# teensy-jst_01_4_v5.net
KiCad netlist of a schematic drawn in EAGLE
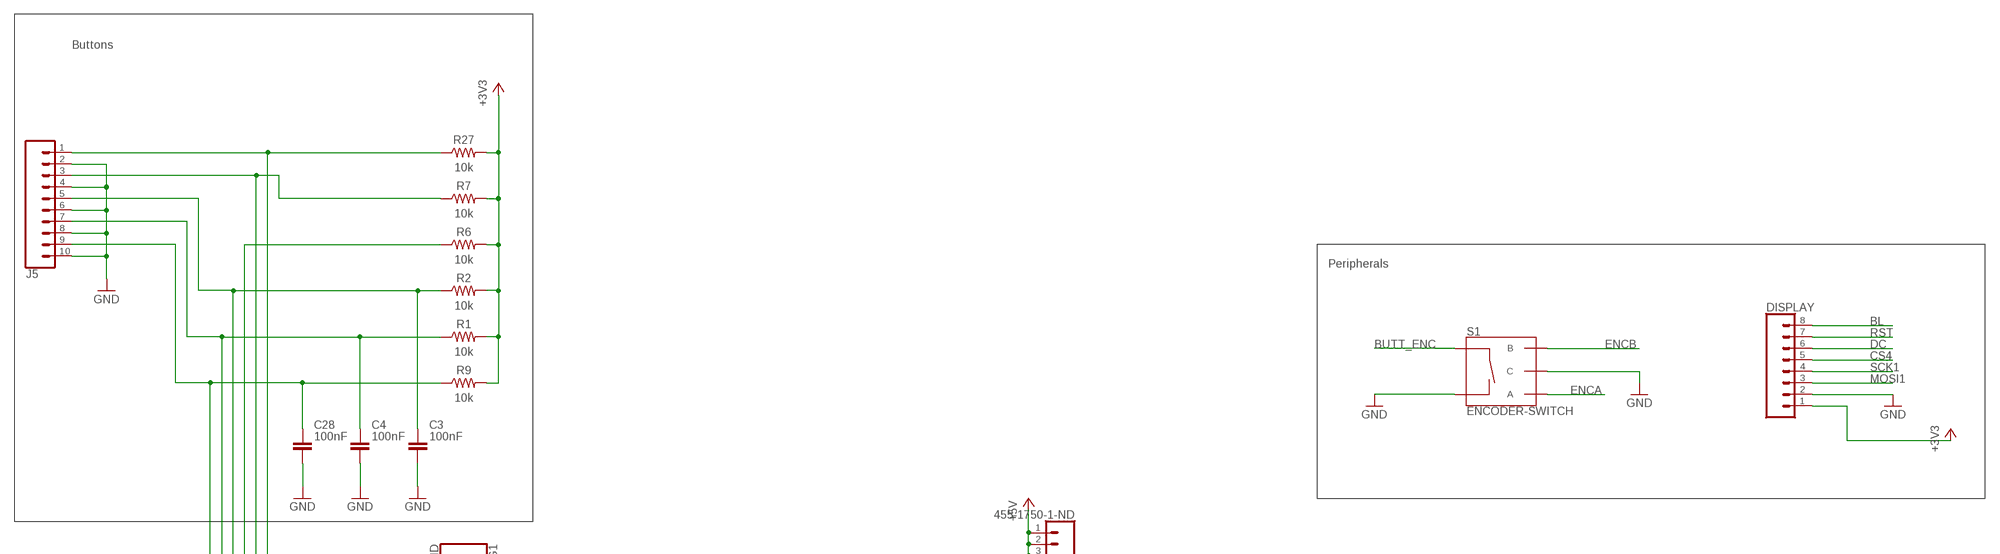
[diagram p0: schematic, sheet 1, part 1 of 3]
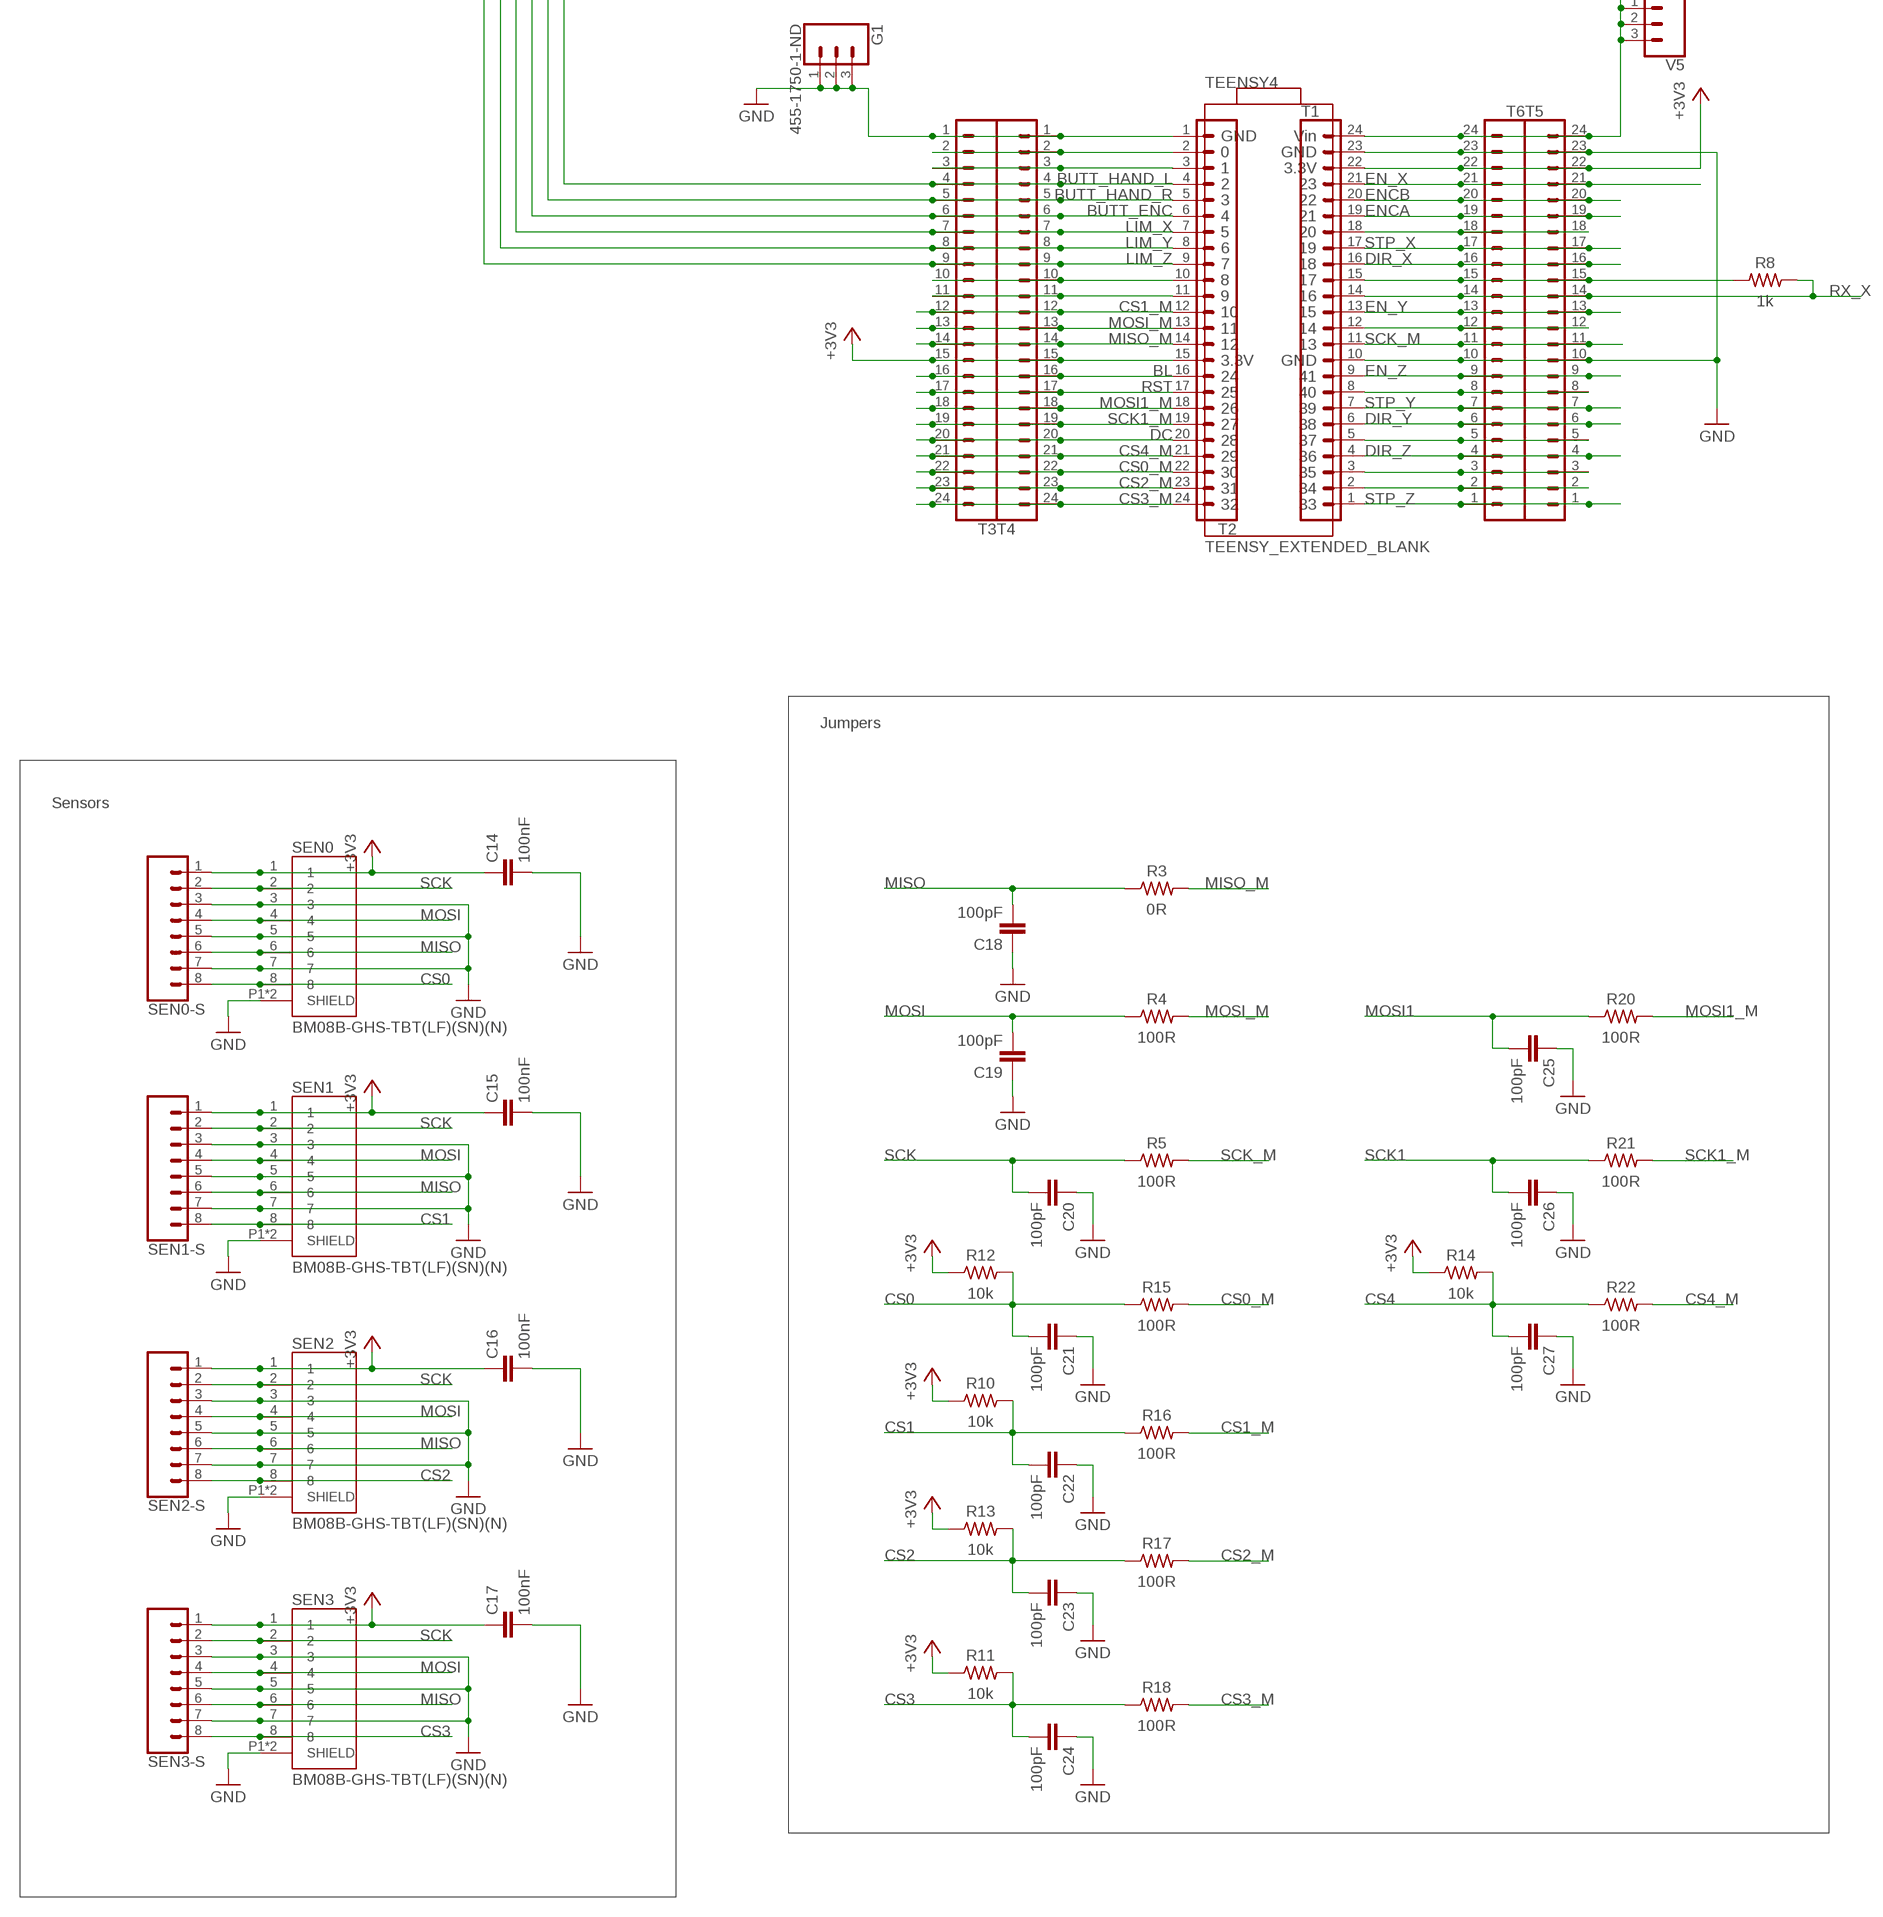
[diagram p1: schematic, sheet 1, part 2 of 3]
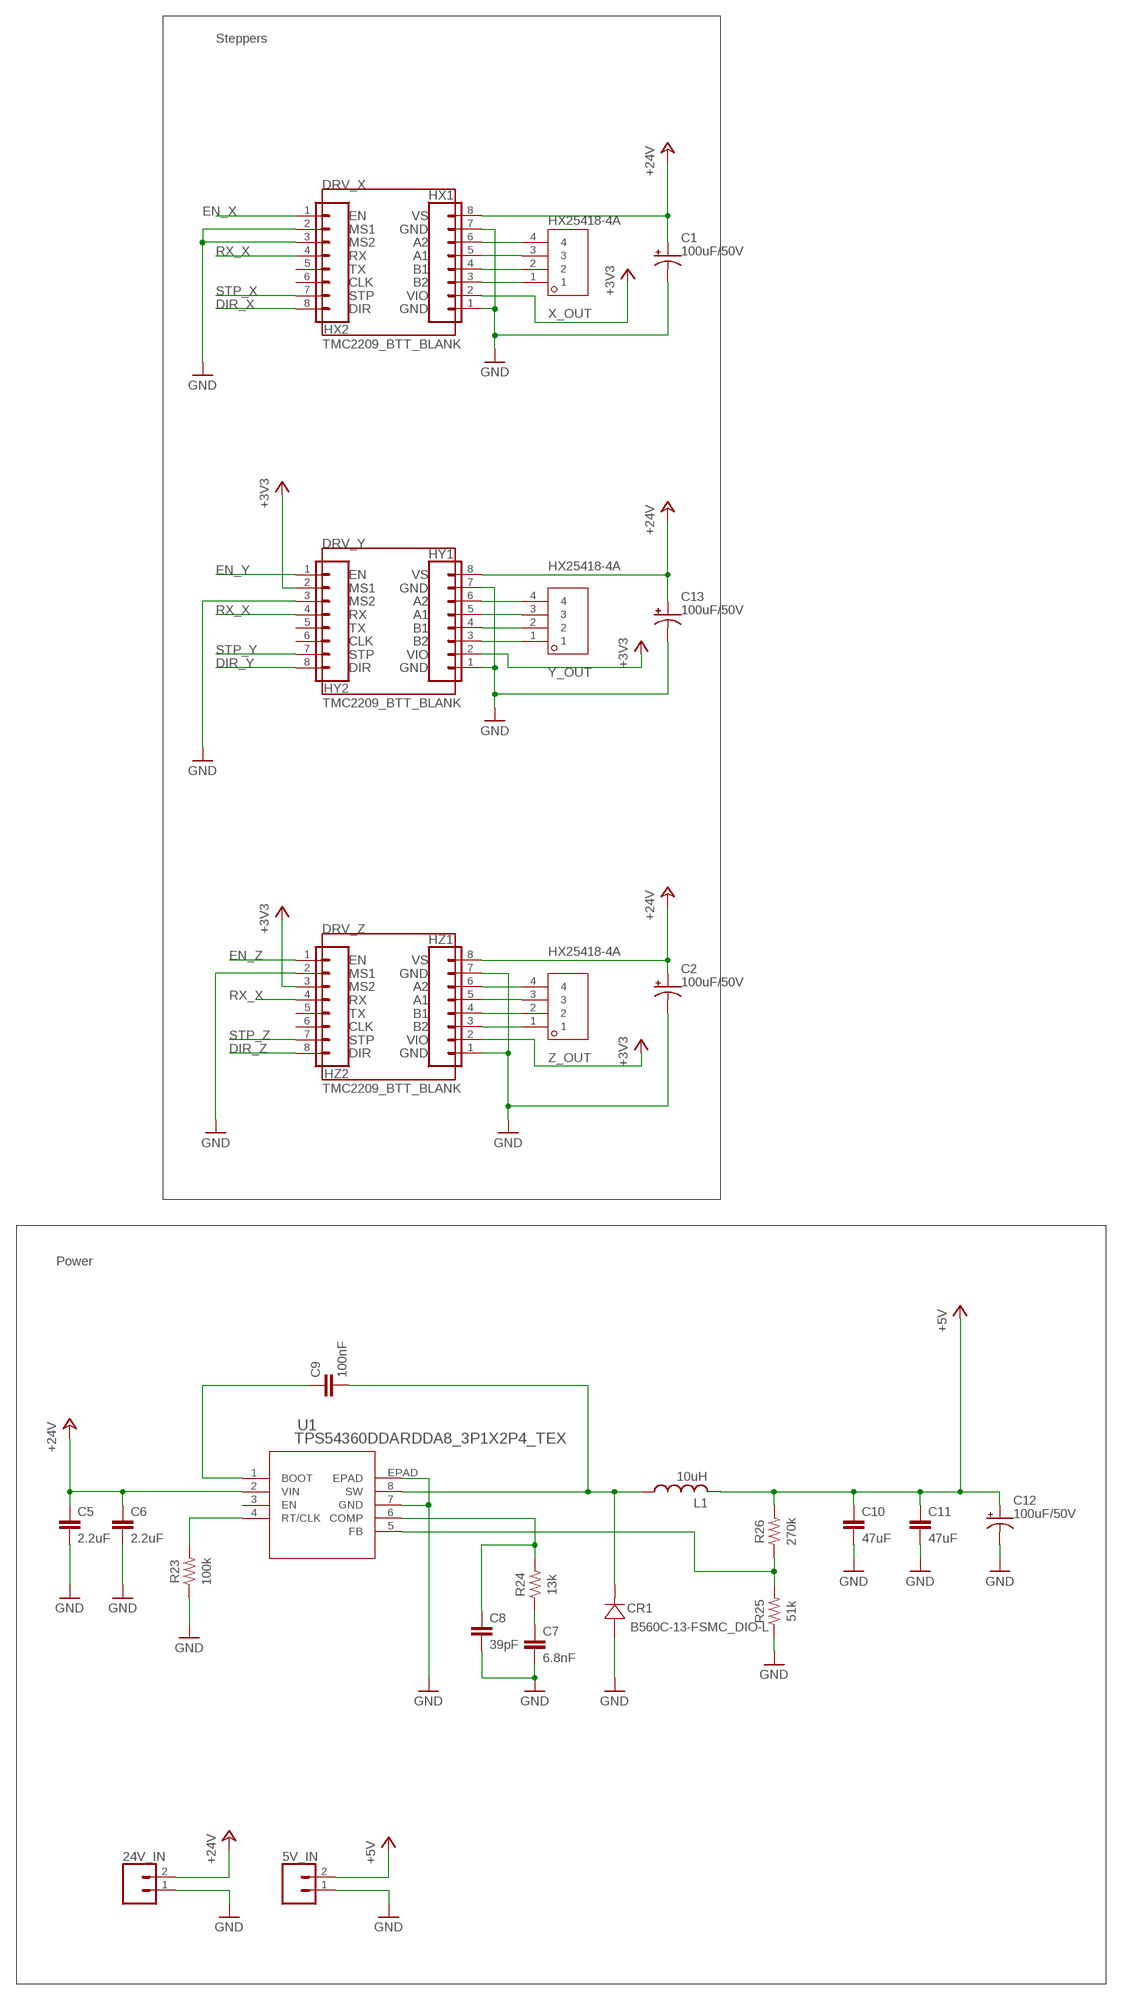
[diagram p2: schematic, sheet 1, part 3 of 3]

(export (version "E")
  (design (tool "Eeschema 10.0.6"))
  (components
    (comp (ref "5V_IN")
      (value "CONN_025MM")
      (footprint "eagle-import:SCREWTERMINAL-5MM-2")
      (libsource (lib "eagle-import") (part "CONN_025MM"))
    )
    (comp (ref "24V_IN")
      (value "CONN_025MM")
      (footprint "eagle-import:SCREWTERMINAL-5MM-2")
      (libsource (lib "eagle-import") (part "CONN_025MM"))
    )
    (comp (ref "C1")
      (value "100uF/50V")
      (footprint "eagle-import:PANASONIC_D")
      (libsource (lib "eagle-import") (part "CPOL-USD"))
    )
    (comp (ref "C2")
      (value "100uF/50V")
      (footprint "eagle-import:PANASONIC_D")
      (libsource (lib "eagle-import") (part "CPOL-USD"))
    )
    (comp (ref "C3")
      (value "100nF")
      (footprint "eagle-import:C0603")
      (libsource (lib "eagle-import") (part "C-EUC0603"))
    )
    (comp (ref "C4")
      (value "100nF")
      (footprint "eagle-import:C0603")
      (libsource (lib "eagle-import") (part "C-EUC0603"))
    )
    (comp (ref "C5")
      (value "2.2uF")
      (footprint "eagle-import:C0603")
      (libsource (lib "eagle-import") (part "C-EUC0603"))
    )
    (comp (ref "C6")
      (value "2.2uF")
      (footprint "eagle-import:C0603")
      (libsource (lib "eagle-import") (part "C-EUC0603"))
    )
    (comp (ref "C7")
      (value "6.8nF")
      (footprint "eagle-import:C0603")
      (libsource (lib "eagle-import") (part "C-EUC0603"))
    )
    (comp (ref "C8")
      (value "39pF")
      (footprint "eagle-import:C0402")
      (libsource (lib "eagle-import") (part "C-EUC0402"))
    )
    (comp (ref "C9")
      (value "100nF")
      (footprint "eagle-import:C0402")
      (libsource (lib "eagle-import") (part "C-EUC0402"))
    )
    (comp (ref "C10")
      (value "47uF")
      (footprint "eagle-import:C0805")
      (libsource (lib "eagle-import") (part "C-EUC0805"))
    )
    (comp (ref "C11")
      (value "47uF")
      (footprint "eagle-import:C0805")
      (libsource (lib "eagle-import") (part "C-EUC0805"))
    )
    (comp (ref "C12")
      (value "100uF/50V")
      (footprint "eagle-import:PANASONIC_D")
      (libsource (lib "eagle-import") (part "CPOL-USD"))
    )
    (comp (ref "C13")
      (value "100uF/50V")
      (footprint "eagle-import:PANASONIC_D")
      (libsource (lib "eagle-import") (part "CPOL-USD"))
    )
    (comp (ref "C14")
      (value "100nF")
      (footprint "eagle-import:C0402")
      (libsource (lib "eagle-import") (part "C-EUC0402"))
    )
    (comp (ref "C15")
      (value "100nF")
      (footprint "eagle-import:C0402")
      (libsource (lib "eagle-import") (part "C-EUC0402"))
    )
    (comp (ref "C16")
      (value "100nF")
      (footprint "eagle-import:C0402")
      (libsource (lib "eagle-import") (part "C-EUC0402"))
    )
    (comp (ref "C17")
      (value "100nF")
      (footprint "eagle-import:C0402")
      (libsource (lib "eagle-import") (part "C-EUC0402"))
    )
    (comp (ref "C18")
      (value "100pF")
      (footprint "eagle-import:C0402K")
      (libsource (lib "eagle-import") (part "C-EUC0402K"))
    )
    (comp (ref "C19")
      (value "100pF")
      (footprint "eagle-import:C0402K")
      (libsource (lib "eagle-import") (part "C-EUC0402K"))
    )
    (comp (ref "C20")
      (value "100pF")
      (footprint "eagle-import:C0402K")
      (libsource (lib "eagle-import") (part "C-EUC0402K"))
    )
    (comp (ref "C21")
      (value "100pF")
      (footprint "eagle-import:C0402K")
      (libsource (lib "eagle-import") (part "C-EUC0402K"))
    )
    (comp (ref "C22")
      (value "100pF")
      (footprint "eagle-import:C0402")
      (libsource (lib "eagle-import") (part "C-EUC0402"))
    )
    (comp (ref "C23")
      (value "100pF")
      (footprint "eagle-import:C0402K")
      (libsource (lib "eagle-import") (part "C-EUC0402K"))
    )
    (comp (ref "C24")
      (value "100pF")
      (footprint "eagle-import:C0402K")
      (libsource (lib "eagle-import") (part "C-EUC0402K"))
    )
    (comp (ref "C25")
      (value "100pF")
      (footprint "eagle-import:C0402K")
      (libsource (lib "eagle-import") (part "C-EUC0402K"))
    )
    (comp (ref "C26")
      (value "100pF")
      (footprint "eagle-import:C0402K")
      (libsource (lib "eagle-import") (part "C-EUC0402K"))
    )
    (comp (ref "C27")
      (value "100pF")
      (footprint "eagle-import:C0402K")
      (libsource (lib "eagle-import") (part "C-EUC0402K"))
    )
    (comp (ref "C28")
      (value "100nF")
      (footprint "eagle-import:C0603")
      (libsource (lib "eagle-import") (part "C-EUC0603"))
    )
    (comp (ref "CR1")
      (value "B560C-13-FSMC_DIO-L")
      (footprint "eagle-import:SMC_DIO-L")
      (fields
        (field (name "MANUFACTURER_PART_NUMBER") "B560C-13-F")
        (field (name "COPYRIGHT") "Copyright (C) 2024 Ultra Librarian. All rights reserved.")
      )
      (libsource (lib "eagle-import") (part "B560C-13-FSMC_DIO-L"))
    )
    (comp (ref "DISPLAY")
      (value "CONN_08\"")
      (footprint "eagle-import:1X08")
      (libsource (lib "eagle-import") (part "CONN_08{dblquote}"))
    )
    (comp (ref "DRV_X")
      (value "TMC2209_BTT_BLANK")
      (footprint "eagle-import:MODULE_TMC2209_BTT_BLANK")
      (libsource (lib "eagle-import") (part "TMC2209_BTT_BLANK"))
    )
    (comp (ref "DRV_Y")
      (value "TMC2209_BTT_BLANK")
      (footprint "eagle-import:MODULE_TMC2209_BTT_BLANK")
      (libsource (lib "eagle-import") (part "TMC2209_BTT_BLANK"))
    )
    (comp (ref "DRV_Z")
      (value "TMC2209_BTT_BLANK")
      (footprint "eagle-import:MODULE_TMC2209_BTT_BLANK")
      (libsource (lib "eagle-import") (part "TMC2209_BTT_BLANK"))
    )
    (comp (ref "G1")
      (value "455-1750-1-ND")
      (footprint "eagle-import:1X03")
      (libsource (lib "eagle-import") (part "CONN_03"))
    )
    (comp (ref "HX1")
      (value "CONN_08\"")
      (footprint "eagle-import:1X08")
      (libsource (lib "eagle-import") (part "CONN_08{dblquote}"))
    )
    (comp (ref "HX2")
      (value "CONN_08\"")
      (footprint "eagle-import:1X08")
      (libsource (lib "eagle-import") (part "CONN_08{dblquote}"))
    )
    (comp (ref "HY1")
      (value "CONN_08\"")
      (footprint "eagle-import:1X08")
      (libsource (lib "eagle-import") (part "CONN_08{dblquote}"))
    )
    (comp (ref "HY2")
      (value "CONN_08\"")
      (footprint "eagle-import:1X08")
      (libsource (lib "eagle-import") (part "CONN_08{dblquote}"))
    )
    (comp (ref "HZ1")
      (value "CONN_08\"")
      (footprint "eagle-import:1X08")
      (libsource (lib "eagle-import") (part "CONN_08{dblquote}"))
    )
    (comp (ref "HZ2")
      (value "CONN_08\"")
      (footprint "eagle-import:1X08")
      (libsource (lib "eagle-import") (part "CONN_08{dblquote}"))
    )
    (comp (ref "J5")
      (value "CONN_10\"")
      (footprint "eagle-import:1X10")
      (libsource (lib "eagle-import") (part "CONN_10{dblquote}"))
    )
    (comp (ref "L1")
      (value "10uH")
      (footprint "eagle-import:MWSA0503S-100MT")
      (libsource (lib "eagle-import") (part "L-USMWSA0503S-100MT"))
    )
    (comp (ref "R1")
      (value "10k")
      (footprint "eagle-import:RESC1608X60")
      (libsource (lib "eagle-import") (part "R-USCHIP-0603(1608-METRIC)_"))
    )
    (comp (ref "R2")
      (value "10k")
      (footprint "eagle-import:RESC1608X60")
      (libsource (lib "eagle-import") (part "R-USCHIP-0603(1608-METRIC)_"))
    )
    (comp (ref "R3")
      (value "0R")
      (footprint "eagle-import:RESC1608X60")
      (libsource (lib "eagle-import") (part "R-USCHIP-0603(1608-METRIC)_"))
    )
    (comp (ref "R4")
      (value "100R")
      (footprint "eagle-import:RESC1608X60")
      (libsource (lib "eagle-import") (part "R-USCHIP-0603(1608-METRIC)_"))
    )
    (comp (ref "R5")
      (value "100R")
      (footprint "eagle-import:RESC1608X60")
      (libsource (lib "eagle-import") (part "R-USCHIP-0603(1608-METRIC)_"))
    )
    (comp (ref "R6")
      (value "10k")
      (footprint "eagle-import:RESC1608X60")
      (libsource (lib "eagle-import") (part "R-USCHIP-0603(1608-METRIC)_"))
    )
    (comp (ref "R7")
      (value "10k")
      (footprint "eagle-import:RESC1608X60")
      (libsource (lib "eagle-import") (part "R-USCHIP-0603(1608-METRIC)_"))
    )
    (comp (ref "R8")
      (value "1k")
      (footprint "eagle-import:RESC1608X60")
      (libsource (lib "eagle-import") (part "R-USCHIP-0603(1608-METRIC)_"))
    )
    (comp (ref "R9")
      (value "10k")
      (footprint "eagle-import:RESC1608X60")
      (libsource (lib "eagle-import") (part "R-USCHIP-0603(1608-METRIC)_"))
    )
    (comp (ref "R10")
      (value "10k")
      (footprint "eagle-import:RESC1608X60")
      (libsource (lib "eagle-import") (part "R-USCHIP-0603(1608-METRIC)_"))
    )
    (comp (ref "R11")
      (value "10k")
      (footprint "eagle-import:RESC1608X60")
      (libsource (lib "eagle-import") (part "R-USCHIP-0603(1608-METRIC)_"))
    )
    (comp (ref "R12")
      (value "10k")
      (footprint "eagle-import:RESC1608X60")
      (libsource (lib "eagle-import") (part "R-USCHIP-0603(1608-METRIC)_"))
    )
    (comp (ref "R13")
      (value "10k")
      (footprint "eagle-import:RESC1608X60")
      (libsource (lib "eagle-import") (part "R-USCHIP-0603(1608-METRIC)_"))
    )
    (comp (ref "R14")
      (value "10k")
      (footprint "eagle-import:RESC1608X60")
      (libsource (lib "eagle-import") (part "R-USCHIP-0603(1608-METRIC)_"))
    )
    (comp (ref "R15")
      (value "100R")
      (footprint "eagle-import:RESC1608X60")
      (libsource (lib "eagle-import") (part "R-USCHIP-0603(1608-METRIC)_"))
    )
    (comp (ref "R16")
      (value "100R")
      (footprint "eagle-import:RESC1608X60")
      (libsource (lib "eagle-import") (part "R-USCHIP-0603(1608-METRIC)_"))
    )
    (comp (ref "R17")
      (value "100R")
      (footprint "eagle-import:RESC1608X60")
      (libsource (lib "eagle-import") (part "R-USCHIP-0603(1608-METRIC)_"))
    )
    (comp (ref "R18")
      (value "100R")
      (footprint "eagle-import:RESC1608X60")
      (libsource (lib "eagle-import") (part "R-USCHIP-0603(1608-METRIC)_"))
    )
    (comp (ref "R20")
      (value "100R")
      (footprint "eagle-import:RESC1608X60")
      (libsource (lib "eagle-import") (part "R-USCHIP-0603(1608-METRIC)_"))
    )
    (comp (ref "R21")
      (value "100R")
      (footprint "eagle-import:RESC1608X60")
      (libsource (lib "eagle-import") (part "R-USCHIP-0603(1608-METRIC)_"))
    )
    (comp (ref "R22")
      (value "100R")
      (footprint "eagle-import:RESC1608X60")
      (libsource (lib "eagle-import") (part "R-USCHIP-0603(1608-METRIC)_"))
    )
    (comp (ref "R23")
      (value "100k")
      (footprint "eagle-import:RESC1005X40")
      (libsource (lib "eagle-import") (part "R-USCHIP-0402(1005-METRIC)_"))
    )
    (comp (ref "R24")
      (value "13k")
      (footprint "eagle-import:RESC1608X60")
      (libsource (lib "eagle-import") (part "R-USCHIP-0603(1608-METRIC)_"))
    )
    (comp (ref "R25")
      (value "51k")
      (footprint "eagle-import:RESC1608X60")
      (libsource (lib "eagle-import") (part "R-USCHIP-0603(1608-METRIC)_"))
    )
    (comp (ref "R26")
      (value "270k")
      (footprint "eagle-import:RESC1005X40")
      (libsource (lib "eagle-import") (part "R-USCHIP-0402(1005-METRIC)_"))
    )
    (comp (ref "R27")
      (value "10k")
      (footprint "eagle-import:RESC1608X60")
      (libsource (lib "eagle-import") (part "R-USCHIP-0603(1608-METRIC)_"))
    )
    (comp (ref "S1")
      (value "ENCODER-SWITCH")
      (footprint "eagle-import:ROTARY_ENC_PLAIN")
      (libsource (lib "eagle-import") (part "ENCODER-SWITCH"))
    )
    (comp (ref "SEN0")
      (value "BM08B-GHS-TBT(LF)(SN)(N)")
      (footprint "eagle-import:JST_BM08B-GHS-TBT(LF)(SN)(N)")
      (fields (field (name "MF") "JST Sales"))
      (libsource (lib "eagle-import") (part "BM08B-GHS-TBT(LF)(SN)(N)"))
    )
    (comp (ref "SEN0-S")
      (value "CONN_08\"")
      (footprint "eagle-import:1X08")
      (libsource (lib "eagle-import") (part "CONN_08{dblquote}"))
    )
    (comp (ref "SEN1")
      (value "BM08B-GHS-TBT(LF)(SN)(N)")
      (footprint "eagle-import:JST_BM08B-GHS-TBT(LF)(SN)(N)")
      (fields (field (name "MF") "JST Sales"))
      (libsource (lib "eagle-import") (part "BM08B-GHS-TBT(LF)(SN)(N)"))
    )
    (comp (ref "SEN1-S")
      (value "CONN_08\"")
      (footprint "eagle-import:1X08")
      (libsource (lib "eagle-import") (part "CONN_08{dblquote}"))
    )
    (comp (ref "SEN2")
      (value "BM08B-GHS-TBT(LF)(SN)(N)")
      (footprint "eagle-import:JST_BM08B-GHS-TBT(LF)(SN)(N)")
      (fields (field (name "MF") "JST Sales"))
      (libsource (lib "eagle-import") (part "BM08B-GHS-TBT(LF)(SN)(N)"))
    )
    (comp (ref "SEN2-S")
      (value "CONN_08\"")
      (footprint "eagle-import:1X08")
      (libsource (lib "eagle-import") (part "CONN_08{dblquote}"))
    )
    (comp (ref "SEN3")
      (value "BM08B-GHS-TBT(LF)(SN)(N)")
      (footprint "eagle-import:JST_BM08B-GHS-TBT(LF)(SN)(N)")
      (fields (field (name "MF") "JST Sales"))
      (libsource (lib "eagle-import") (part "BM08B-GHS-TBT(LF)(SN)(N)"))
    )
    (comp (ref "SEN3-S")
      (value "CONN_08\"")
      (footprint "eagle-import:1X08")
      (libsource (lib "eagle-import") (part "CONN_08{dblquote}"))
    )
    (comp (ref "T1")
      (value "CONN_24")
      (footprint "eagle-import:1X24")
      (libsource (lib "eagle-import") (part "CONN_24"))
    )
    (comp (ref "T2")
      (value "CONN_24")
      (footprint "eagle-import:1X24")
      (libsource (lib "eagle-import") (part "CONN_24"))
    )
    (comp (ref "T3")
      (value "CONN_24")
      (footprint "eagle-import:1X24")
      (libsource (lib "eagle-import") (part "CONN_24"))
    )
    (comp (ref "T4")
      (value "CONN_24")
      (footprint "eagle-import:1X24")
      (libsource (lib "eagle-import") (part "CONN_24"))
    )
    (comp (ref "T5")
      (value "CONN_24")
      (footprint "eagle-import:1X24")
      (libsource (lib "eagle-import") (part "CONN_24"))
    )
    (comp (ref "T6")
      (value "CONN_24")
      (footprint "eagle-import:1X24")
      (libsource (lib "eagle-import") (part "CONN_24"))
    )
    (comp (ref "TEENSY4")
      (value "TEENSY_EXTENDED_BLANK")
      (footprint "eagle-import:TEENSY_EXTENDED_BLANK")
      (libsource (lib "eagle-import") (part "TEENSY_EXTENDED_BLANK"))
    )
    (comp (ref "U1")
      (value "TPS54360DDARDDA8_3P1X2P4_TEX")
      (footprint "eagle-import:DDA8_3P1X2P4_TEX")
      (fields
        (field (name "MANUFACTURER_PART_NUMBER") "TPS54360DDAR")
        (field (name "COPYRIGHT") "Copyright (C) 2024 Ultra Librarian. All rights reserved.")
      )
      (libsource (lib "eagle-import") (part "TPS54360DDARDDA8_3P1X2P4_TEX"))
    )
    (comp (ref "V5")
      (value "455-1750-1-ND")
      (footprint "eagle-import:1X03")
      (libsource (lib "eagle-import") (part "CONN_03"))
    )
    (comp (ref "X_OUT")
      (value "HX25418-4A")
      (footprint "eagle-import:HX25418-4A")
      (libsource (lib "eagle-import") (part "HX25418-4A"))
    )
    (comp (ref "Y_OUT")
      (value "HX25418-4A")
      (footprint "eagle-import:HX25418-4A")
      (libsource (lib "eagle-import") (part "HX25418-4A"))
    )
    (comp (ref "Z_OUT")
      (value "HX25418-4A")
      (footprint "eagle-import:HX25418-4A")
      (libsource (lib "eagle-import") (part "HX25418-4A"))
    )
  )
  (nets
    (net (code "1") (name "+3V3") (class "Default")
      (node (ref "C14") (pin "1") (pinfunction "1_1") (pintype "passive"))
      (node (ref "C15") (pin "1") (pinfunction "1_1") (pintype "passive"))
      (node (ref "C16") (pin "1") (pinfunction "1_1") (pintype "passive"))
      (node (ref "C17") (pin "1") (pinfunction "1_1") (pintype "passive"))
      (node (ref "DISPLAY") (pin "1") (pinfunction "1_1") (pintype "passive"))
      (node (ref "HX1") (pin "2") (pinfunction "2_2") (pintype "passive"))
      (node (ref "HY1") (pin "2") (pinfunction "2_2") (pintype "passive"))
      (node (ref "HY2") (pin "2") (pinfunction "2_2") (pintype "passive"))
      (node (ref "HZ1") (pin "2") (pinfunction "2_2") (pintype "passive"))
      (node (ref "HZ2") (pin "3") (pinfunction "3_3") (pintype "passive"))
      (node (ref "R1") (pin "2") (pinfunction "2_2") (pintype "passive"))
      (node (ref "R10") (pin "1") (pinfunction "1_1") (pintype "passive"))
      (node (ref "R11") (pin "1") (pinfunction "1_1") (pintype "passive"))
      (node (ref "R12") (pin "1") (pinfunction "1_1") (pintype "passive"))
      (node (ref "R13") (pin "1") (pinfunction "1_1") (pintype "passive"))
      (node (ref "R14") (pin "1") (pinfunction "1_1") (pintype "passive"))
      (node (ref "R2") (pin "2") (pinfunction "2_2") (pintype "passive"))
      (node (ref "R27") (pin "2") (pinfunction "2_2") (pintype "passive"))
      (node (ref "R6") (pin "2") (pinfunction "2_2") (pintype "passive"))
      (node (ref "R7") (pin "2") (pinfunction "2_2") (pintype "passive"))
      (node (ref "R9") (pin "2") (pinfunction "2_2") (pintype "passive"))
      (node (ref "SEN0") (pin "1") (pinfunction "1_1") (pintype "passive"))
      (node (ref "SEN0-S") (pin "1") (pinfunction "1_1") (pintype "passive"))
      (node (ref "SEN1") (pin "1") (pinfunction "1_1") (pintype "passive"))
      (node (ref "SEN1-S") (pin "1") (pinfunction "1_1") (pintype "passive"))
      (node (ref "SEN2") (pin "1") (pinfunction "1_1") (pintype "passive"))
      (node (ref "SEN2-S") (pin "1") (pinfunction "1_1") (pintype "passive"))
      (node (ref "SEN3") (pin "1") (pinfunction "1_1") (pintype "passive"))
      (node (ref "SEN3-S") (pin "1") (pinfunction "1_1") (pintype "passive"))
      (node (ref "T1") (pin "22") (pinfunction "22_22") (pintype "passive"))
      (node (ref "T2") (pin "15") (pinfunction "15_15") (pintype "passive"))
      (node (ref "T3") (pin "15") (pinfunction "15_15") (pintype "passive"))
      (node (ref "T4") (pin "15") (pinfunction "15_15") (pintype "passive"))
      (node (ref "T5") (pin "22") (pinfunction "22_22") (pintype "passive"))
      (node (ref "T6") (pin "22") (pinfunction "22_22") (pintype "passive"))
    )
    (net (code "2") (name "+5V") (class "Default")
      (node (ref "5V_IN") (pin "2") (pinfunction "2_2") (pintype "passive"))
      (node (ref "C10") (pin "1") (pinfunction "1_1") (pintype "passive"))
      (node (ref "C11") (pin "1") (pinfunction "1_1") (pintype "passive"))
      (node (ref "C12") (pin "+") (pinfunction "+_+") (pintype "passive"))
      (node (ref "L1") (pin "2") (pinfunction "2_2") (pintype "passive"))
      (node (ref "R26") (pin "2") (pinfunction "2_2") (pintype "passive"))
      (node (ref "T1") (pin "24") (pinfunction "24_24") (pintype "passive"))
      (node (ref "T5") (pin "24") (pinfunction "24_24") (pintype "passive"))
      (node (ref "T6") (pin "24") (pinfunction "24_24") (pintype "passive"))
      (node (ref "V5") (pin "1") (pinfunction "1_1") (pintype "passive"))
      (node (ref "V5") (pin "2") (pinfunction "2_2") (pintype "passive"))
      (node (ref "V5") (pin "3") (pinfunction "3_3") (pintype "passive"))
    )
    (net (code "3") (name "+24V") (class "Default")
      (node (ref "24V_IN") (pin "2") (pinfunction "2_2") (pintype "passive"))
      (node (ref "C1") (pin "+") (pinfunction "+_+") (pintype "passive"))
      (node (ref "C13") (pin "+") (pinfunction "+_+") (pintype "passive"))
      (node (ref "C2") (pin "+") (pinfunction "+_+") (pintype "passive"))
      (node (ref "C5") (pin "1") (pinfunction "1_1") (pintype "passive"))
      (node (ref "C6") (pin "1") (pinfunction "1_1") (pintype "passive"))
      (node (ref "HX1") (pin "8") (pinfunction "8_8") (pintype "passive"))
      (node (ref "HY1") (pin "8") (pinfunction "8_8") (pintype "passive"))
      (node (ref "HZ1") (pin "8") (pinfunction "8_8") (pintype "passive"))
      (node (ref "U1") (pin "2") (pinfunction "VIN_2") (pintype "input"))
    )
    (net (code "4") (name "/BL") (class "Default")
      (node (ref "DISPLAY") (pin "8") (pinfunction "8_8") (pintype "passive"))
      (node (ref "T2") (pin "16") (pinfunction "16_16") (pintype "passive"))
      (node (ref "T3") (pin "16") (pinfunction "16_16") (pintype "passive"))
      (node (ref "T4") (pin "16") (pinfunction "16_16") (pintype "passive"))
    )
    (net (code "5") (name "/BUTT_ENC") (class "Default")
      (node (ref "R6") (pin "1") (pinfunction "1_1") (pintype "passive"))
      (node (ref "S1") (pin "SW+") (pinfunction "SW+_SW+") (pintype "bidirectional"))
      (node (ref "T2") (pin "6") (pinfunction "6_6") (pintype "passive"))
      (node (ref "T3") (pin "6") (pinfunction "6_6") (pintype "passive"))
      (node (ref "T4") (pin "6") (pinfunction "6_6") (pintype "passive"))
    )
    (net (code "6") (name "/BUTT_HAND_L") (class "Default")
      (node (ref "J5") (pin "1") (pinfunction "1_1") (pintype "passive"))
      (node (ref "R27") (pin "1") (pinfunction "1_1") (pintype "passive"))
      (node (ref "T2") (pin "4") (pinfunction "4_4") (pintype "passive"))
      (node (ref "T3") (pin "4") (pinfunction "4_4") (pintype "passive"))
      (node (ref "T4") (pin "4") (pinfunction "4_4") (pintype "passive"))
    )
    (net (code "7") (name "/BUTT_HAND_R") (class "Default")
      (node (ref "J5") (pin "3") (pinfunction "3_3") (pintype "passive"))
      (node (ref "R7") (pin "1") (pinfunction "1_1") (pintype "passive"))
      (node (ref "T2") (pin "5") (pinfunction "5_5") (pintype "passive"))
      (node (ref "T3") (pin "5") (pinfunction "5_5") (pintype "passive"))
      (node (ref "T4") (pin "5") (pinfunction "5_5") (pintype "passive"))
    )
    (net (code "8") (name "/CS0") (class "Default")
      (node (ref "C21") (pin "2") (pinfunction "2_2") (pintype "passive"))
      (node (ref "R12") (pin "2") (pinfunction "2_2") (pintype "passive"))
      (node (ref "R15") (pin "1") (pinfunction "1_1") (pintype "passive"))
      (node (ref "SEN0") (pin "8") (pinfunction "8_8") (pintype "passive"))
      (node (ref "SEN0-S") (pin "8") (pinfunction "8_8") (pintype "passive"))
    )
    (net (code "9") (name "/CS0_M") (class "Default")
      (node (ref "R15") (pin "2") (pinfunction "2_2") (pintype "passive"))
      (node (ref "T2") (pin "22") (pinfunction "22_22") (pintype "passive"))
      (node (ref "T3") (pin "22") (pinfunction "22_22") (pintype "passive"))
      (node (ref "T4") (pin "22") (pinfunction "22_22") (pintype "passive"))
    )
    (net (code "10") (name "/CS1") (class "Default")
      (node (ref "C22") (pin "2") (pinfunction "2_2") (pintype "passive"))
      (node (ref "R10") (pin "2") (pinfunction "2_2") (pintype "passive"))
      (node (ref "R16") (pin "1") (pinfunction "1_1") (pintype "passive"))
      (node (ref "SEN1") (pin "8") (pinfunction "8_8") (pintype "passive"))
      (node (ref "SEN1-S") (pin "8") (pinfunction "8_8") (pintype "passive"))
    )
    (net (code "11") (name "/CS1_M") (class "Default")
      (node (ref "R16") (pin "2") (pinfunction "2_2") (pintype "passive"))
      (node (ref "T2") (pin "12") (pinfunction "12_12") (pintype "passive"))
      (node (ref "T3") (pin "12") (pinfunction "12_12") (pintype "passive"))
      (node (ref "T4") (pin "12") (pinfunction "12_12") (pintype "passive"))
    )
    (net (code "12") (name "/CS2") (class "Default")
      (node (ref "C23") (pin "2") (pinfunction "2_2") (pintype "passive"))
      (node (ref "R13") (pin "2") (pinfunction "2_2") (pintype "passive"))
      (node (ref "R17") (pin "1") (pinfunction "1_1") (pintype "passive"))
      (node (ref "SEN2") (pin "8") (pinfunction "8_8") (pintype "passive"))
      (node (ref "SEN2-S") (pin "8") (pinfunction "8_8") (pintype "passive"))
    )
    (net (code "13") (name "/CS2_M") (class "Default")
      (node (ref "R17") (pin "2") (pinfunction "2_2") (pintype "passive"))
      (node (ref "T2") (pin "23") (pinfunction "23_23") (pintype "passive"))
      (node (ref "T3") (pin "23") (pinfunction "23_23") (pintype "passive"))
      (node (ref "T4") (pin "23") (pinfunction "23_23") (pintype "passive"))
    )
    (net (code "14") (name "/CS3") (class "Default")
      (node (ref "C24") (pin "2") (pinfunction "2_2") (pintype "passive"))
      (node (ref "R11") (pin "2") (pinfunction "2_2") (pintype "passive"))
      (node (ref "R18") (pin "1") (pinfunction "1_1") (pintype "passive"))
      (node (ref "SEN3") (pin "8") (pinfunction "8_8") (pintype "passive"))
      (node (ref "SEN3-S") (pin "8") (pinfunction "8_8") (pintype "passive"))
    )
    (net (code "15") (name "/CS3_M") (class "Default")
      (node (ref "R18") (pin "2") (pinfunction "2_2") (pintype "passive"))
      (node (ref "T2") (pin "24") (pinfunction "24_24") (pintype "passive"))
      (node (ref "T3") (pin "24") (pinfunction "24_24") (pintype "passive"))
      (node (ref "T4") (pin "24") (pinfunction "24_24") (pintype "passive"))
    )
    (net (code "16") (name "/CS4") (class "Default")
      (node (ref "C27") (pin "2") (pinfunction "2_2") (pintype "passive"))
      (node (ref "DISPLAY") (pin "5") (pinfunction "5_5") (pintype "passive"))
      (node (ref "R14") (pin "2") (pinfunction "2_2") (pintype "passive"))
      (node (ref "R22") (pin "1") (pinfunction "1_1") (pintype "passive"))
    )
    (net (code "17") (name "/CS4_M") (class "Default")
      (node (ref "R22") (pin "2") (pinfunction "2_2") (pintype "passive"))
      (node (ref "T2") (pin "21") (pinfunction "21_21") (pintype "passive"))
      (node (ref "T3") (pin "21") (pinfunction "21_21") (pintype "passive"))
      (node (ref "T4") (pin "21") (pinfunction "21_21") (pintype "passive"))
    )
    (net (code "18") (name "/DC") (class "Default")
      (node (ref "DISPLAY") (pin "6") (pinfunction "6_6") (pintype "passive"))
      (node (ref "T2") (pin "20") (pinfunction "20_20") (pintype "passive"))
      (node (ref "T3") (pin "20") (pinfunction "20_20") (pintype "passive"))
      (node (ref "T4") (pin "20") (pinfunction "20_20") (pintype "passive"))
    )
    (net (code "19") (name "/DIR_X") (class "Default")
      (node (ref "HX2") (pin "8") (pinfunction "8_8") (pintype "passive"))
      (node (ref "T1") (pin "16") (pinfunction "16_16") (pintype "passive"))
      (node (ref "T5") (pin "16") (pinfunction "16_16") (pintype "passive"))
      (node (ref "T6") (pin "16") (pinfunction "16_16") (pintype "passive"))
    )
    (net (code "20") (name "/DIR_Y") (class "Default")
      (node (ref "HY2") (pin "8") (pinfunction "8_8") (pintype "passive"))
      (node (ref "T1") (pin "6") (pinfunction "6_6") (pintype "passive"))
      (node (ref "T5") (pin "6") (pinfunction "6_6") (pintype "passive"))
      (node (ref "T6") (pin "6") (pinfunction "6_6") (pintype "passive"))
    )
    (net (code "21") (name "/DIR_Z") (class "Default")
      (node (ref "HZ2") (pin "8") (pinfunction "8_8") (pintype "passive"))
      (node (ref "T1") (pin "4") (pinfunction "4_4") (pintype "passive"))
      (node (ref "T5") (pin "4") (pinfunction "4_4") (pintype "passive"))
      (node (ref "T6") (pin "4") (pinfunction "4_4") (pintype "passive"))
    )
    (net (code "22") (name "/ENCA") (class "Default")
      (node (ref "S1") (pin "A") (pinfunction "A_A") (pintype "bidirectional"))
      (node (ref "T1") (pin "19") (pinfunction "19_19") (pintype "passive"))
      (node (ref "T5") (pin "19") (pinfunction "19_19") (pintype "passive"))
      (node (ref "T6") (pin "19") (pinfunction "19_19") (pintype "passive"))
    )
    (net (code "23") (name "/ENCB") (class "Default")
      (node (ref "S1") (pin "B") (pinfunction "B_B") (pintype "bidirectional"))
      (node (ref "T1") (pin "20") (pinfunction "20_20") (pintype "passive"))
      (node (ref "T5") (pin "20") (pinfunction "20_20") (pintype "passive"))
      (node (ref "T6") (pin "20") (pinfunction "20_20") (pintype "passive"))
    )
    (net (code "24") (name "/EN_X") (class "Default")
      (node (ref "HX2") (pin "1") (pinfunction "1_1") (pintype "passive"))
      (node (ref "T1") (pin "21") (pinfunction "21_21") (pintype "passive"))
      (node (ref "T5") (pin "21") (pinfunction "21_21") (pintype "passive"))
      (node (ref "T6") (pin "21") (pinfunction "21_21") (pintype "passive"))
    )
    (net (code "25") (name "/EN_Y") (class "Default")
      (node (ref "HY2") (pin "1") (pinfunction "1_1") (pintype "passive"))
      (node (ref "T1") (pin "13") (pinfunction "13_13") (pintype "passive"))
      (node (ref "T5") (pin "13") (pinfunction "13_13") (pintype "passive"))
      (node (ref "T6") (pin "13") (pinfunction "13_13") (pintype "passive"))
    )
    (net (code "26") (name "/EN_Z") (class "Default")
      (node (ref "HZ2") (pin "1") (pinfunction "1_1") (pintype "passive"))
      (node (ref "T1") (pin "9") (pinfunction "9_9") (pintype "passive"))
      (node (ref "T5") (pin "9") (pinfunction "9_9") (pintype "passive"))
      (node (ref "T6") (pin "9") (pinfunction "9_9") (pintype "passive"))
    )
    (net (code "27") (name "/LIM_X") (class "Default")
      (node (ref "C3") (pin "1") (pinfunction "1_1") (pintype "passive"))
      (node (ref "J5") (pin "5") (pinfunction "5_5") (pintype "passive"))
      (node (ref "R2") (pin "1") (pinfunction "1_1") (pintype "passive"))
      (node (ref "T2") (pin "7") (pinfunction "7_7") (pintype "passive"))
      (node (ref "T3") (pin "7") (pinfunction "7_7") (pintype "passive"))
      (node (ref "T4") (pin "7") (pinfunction "7_7") (pintype "passive"))
    )
    (net (code "28") (name "/LIM_Y") (class "Default")
      (node (ref "C4") (pin "1") (pinfunction "1_1") (pintype "passive"))
      (node (ref "J5") (pin "7") (pinfunction "7_7") (pintype "passive"))
      (node (ref "R1") (pin "1") (pinfunction "1_1") (pintype "passive"))
      (node (ref "T2") (pin "8") (pinfunction "8_8") (pintype "passive"))
      (node (ref "T3") (pin "8") (pinfunction "8_8") (pintype "passive"))
      (node (ref "T4") (pin "8") (pinfunction "8_8") (pintype "passive"))
    )
    (net (code "29") (name "/LIM_Z") (class "Default")
      (node (ref "C28") (pin "1") (pinfunction "1_1") (pintype "passive"))
      (node (ref "J5") (pin "9") (pinfunction "9_9") (pintype "passive"))
      (node (ref "R9") (pin "1") (pinfunction "1_1") (pintype "passive"))
      (node (ref "T2") (pin "9") (pinfunction "9_9") (pintype "passive"))
      (node (ref "T3") (pin "9") (pinfunction "9_9") (pintype "passive"))
      (node (ref "T4") (pin "9") (pinfunction "9_9") (pintype "passive"))
    )
    (net (code "30") (name "/MISO") (class "Default")
      (node (ref "C18") (pin "2") (pinfunction "2_2") (pintype "passive"))
      (node (ref "R3") (pin "1") (pinfunction "1_1") (pintype "passive"))
      (node (ref "SEN0") (pin "6") (pinfunction "6_6") (pintype "passive"))
      (node (ref "SEN0-S") (pin "6") (pinfunction "6_6") (pintype "passive"))
      (node (ref "SEN1") (pin "6") (pinfunction "6_6") (pintype "passive"))
      (node (ref "SEN1-S") (pin "6") (pinfunction "6_6") (pintype "passive"))
      (node (ref "SEN2") (pin "6") (pinfunction "6_6") (pintype "passive"))
      (node (ref "SEN2-S") (pin "6") (pinfunction "6_6") (pintype "passive"))
      (node (ref "SEN3") (pin "6") (pinfunction "6_6") (pintype "passive"))
      (node (ref "SEN3-S") (pin "6") (pinfunction "6_6") (pintype "passive"))
    )
    (net (code "31") (name "/MISO_M") (class "Default")
      (node (ref "R3") (pin "2") (pinfunction "2_2") (pintype "passive"))
      (node (ref "T2") (pin "14") (pinfunction "14_14") (pintype "passive"))
      (node (ref "T3") (pin "14") (pinfunction "14_14") (pintype "passive"))
      (node (ref "T4") (pin "14") (pinfunction "14_14") (pintype "passive"))
    )
    (net (code "32") (name "/MOSI") (class "Default")
      (node (ref "C19") (pin "2") (pinfunction "2_2") (pintype "passive"))
      (node (ref "R4") (pin "1") (pinfunction "1_1") (pintype "passive"))
      (node (ref "SEN0") (pin "4") (pinfunction "4_4") (pintype "passive"))
      (node (ref "SEN0-S") (pin "4") (pinfunction "4_4") (pintype "passive"))
      (node (ref "SEN1") (pin "4") (pinfunction "4_4") (pintype "passive"))
      (node (ref "SEN1-S") (pin "4") (pinfunction "4_4") (pintype "passive"))
      (node (ref "SEN2") (pin "4") (pinfunction "4_4") (pintype "passive"))
      (node (ref "SEN2-S") (pin "4") (pinfunction "4_4") (pintype "passive"))
      (node (ref "SEN3") (pin "4") (pinfunction "4_4") (pintype "passive"))
      (node (ref "SEN3-S") (pin "4") (pinfunction "4_4") (pintype "passive"))
    )
    (net (code "33") (name "/MOSI1") (class "Default")
      (node (ref "C25") (pin "2") (pinfunction "2_2") (pintype "passive"))
      (node (ref "DISPLAY") (pin "3") (pinfunction "3_3") (pintype "passive"))
      (node (ref "R20") (pin "1") (pinfunction "1_1") (pintype "passive"))
    )
    (net (code "34") (name "/MOSI1_M") (class "Default")
      (node (ref "R20") (pin "2") (pinfunction "2_2") (pintype "passive"))
      (node (ref "T2") (pin "18") (pinfunction "18_18") (pintype "passive"))
      (node (ref "T3") (pin "18") (pinfunction "18_18") (pintype "passive"))
      (node (ref "T4") (pin "18") (pinfunction "18_18") (pintype "passive"))
    )
    (net (code "35") (name "/MOSI_M") (class "Default")
      (node (ref "R4") (pin "2") (pinfunction "2_2") (pintype "passive"))
      (node (ref "T2") (pin "13") (pinfunction "13_13") (pintype "passive"))
      (node (ref "T3") (pin "13") (pinfunction "13_13") (pintype "passive"))
      (node (ref "T4") (pin "13") (pinfunction "13_13") (pintype "passive"))
    )
    (net (code "36") (name "/RST") (class "Default")
      (node (ref "DISPLAY") (pin "7") (pinfunction "7_7") (pintype "passive"))
      (node (ref "T2") (pin "17") (pinfunction "17_17") (pintype "passive"))
      (node (ref "T3") (pin "17") (pinfunction "17_17") (pintype "passive"))
      (node (ref "T4") (pin "17") (pinfunction "17_17") (pintype "passive"))
    )
    (net (code "37") (name "/RX_X") (class "Default")
      (node (ref "HX2") (pin "4") (pinfunction "4_4") (pintype "passive"))
      (node (ref "HY2") (pin "4") (pinfunction "4_4") (pintype "passive"))
      (node (ref "HZ2") (pin "4") (pinfunction "4_4") (pintype "passive"))
      (node (ref "R8") (pin "2") (pinfunction "2_2") (pintype "passive"))
      (node (ref "T1") (pin "14") (pinfunction "14_14") (pintype "passive"))
      (node (ref "T5") (pin "14") (pinfunction "14_14") (pintype "passive"))
      (node (ref "T6") (pin "14") (pinfunction "14_14") (pintype "passive"))
    )
    (net (code "38") (name "/SCK") (class "Default")
      (node (ref "C20") (pin "2") (pinfunction "2_2") (pintype "passive"))
      (node (ref "R5") (pin "1") (pinfunction "1_1") (pintype "passive"))
      (node (ref "SEN0") (pin "2") (pinfunction "2_2") (pintype "passive"))
      (node (ref "SEN0-S") (pin "2") (pinfunction "2_2") (pintype "passive"))
      (node (ref "SEN1") (pin "2") (pinfunction "2_2") (pintype "passive"))
      (node (ref "SEN1-S") (pin "2") (pinfunction "2_2") (pintype "passive"))
      (node (ref "SEN2") (pin "2") (pinfunction "2_2") (pintype "passive"))
      (node (ref "SEN2-S") (pin "2") (pinfunction "2_2") (pintype "passive"))
      (node (ref "SEN3") (pin "2") (pinfunction "2_2") (pintype "passive"))
      (node (ref "SEN3-S") (pin "2") (pinfunction "2_2") (pintype "passive"))
    )
    (net (code "39") (name "/SCK1") (class "Default")
      (node (ref "C26") (pin "2") (pinfunction "2_2") (pintype "passive"))
      (node (ref "DISPLAY") (pin "4") (pinfunction "4_4") (pintype "passive"))
      (node (ref "R21") (pin "1") (pinfunction "1_1") (pintype "passive"))
    )
    (net (code "40") (name "/SCK1_M") (class "Default")
      (node (ref "R21") (pin "2") (pinfunction "2_2") (pintype "passive"))
      (node (ref "T2") (pin "19") (pinfunction "19_19") (pintype "passive"))
      (node (ref "T3") (pin "19") (pinfunction "19_19") (pintype "passive"))
      (node (ref "T4") (pin "19") (pinfunction "19_19") (pintype "passive"))
    )
    (net (code "41") (name "/SCK_M") (class "Default")
      (node (ref "R5") (pin "2") (pinfunction "2_2") (pintype "passive"))
      (node (ref "T1") (pin "11") (pinfunction "11_11") (pintype "passive"))
      (node (ref "T5") (pin "11") (pinfunction "11_11") (pintype "passive"))
      (node (ref "T6") (pin "11") (pinfunction "11_11") (pintype "passive"))
    )
    (net (code "42") (name "/STP_X") (class "Default")
      (node (ref "HX2") (pin "7") (pinfunction "7_7") (pintype "passive"))
      (node (ref "T1") (pin "17") (pinfunction "17_17") (pintype "passive"))
      (node (ref "T5") (pin "17") (pinfunction "17_17") (pintype "passive"))
      (node (ref "T6") (pin "17") (pinfunction "17_17") (pintype "passive"))
    )
    (net (code "43") (name "/STP_Y") (class "Default")
      (node (ref "HY2") (pin "7") (pinfunction "7_7") (pintype "passive"))
      (node (ref "T1") (pin "7") (pinfunction "7_7") (pintype "passive"))
      (node (ref "T5") (pin "7") (pinfunction "7_7") (pintype "passive"))
      (node (ref "T6") (pin "7") (pinfunction "7_7") (pintype "passive"))
    )
    (net (code "44") (name "/STP_Z") (class "Default")
      (node (ref "HZ2") (pin "7") (pinfunction "7_7") (pintype "passive"))
      (node (ref "T1") (pin "1") (pinfunction "1_1") (pintype "passive"))
      (node (ref "T5") (pin "1") (pinfunction "1_1") (pintype "passive"))
      (node (ref "T6") (pin "1") (pinfunction "1_1") (pintype "passive"))
    )
    (net (code "45") (name "GND") (class "Default")
      (node (ref "24V_IN") (pin "1") (pinfunction "1_1") (pintype "passive"))
      (node (ref "5V_IN") (pin "1") (pinfunction "1_1") (pintype "passive"))
      (node (ref "C1") (pin "-") (pinfunction "-_-") (pintype "passive"))
      (node (ref "C10") (pin "2") (pinfunction "2_2") (pintype "passive"))
      (node (ref "C11") (pin "2") (pinfunction "2_2") (pintype "passive"))
      (node (ref "C12") (pin "-") (pinfunction "-_-") (pintype "passive"))
      (node (ref "C13") (pin "-") (pinfunction "-_-") (pintype "passive"))
      (node (ref "C14") (pin "2") (pinfunction "2_2") (pintype "passive"))
      (node (ref "C15") (pin "2") (pinfunction "2_2") (pintype "passive"))
      (node (ref "C16") (pin "2") (pinfunction "2_2") (pintype "passive"))
      (node (ref "C17") (pin "2") (pinfunction "2_2") (pintype "passive"))
      (node (ref "C18") (pin "1") (pinfunction "1_1") (pintype "passive"))
      (node (ref "C19") (pin "1") (pinfunction "1_1") (pintype "passive"))
      (node (ref "C2") (pin "-") (pinfunction "-_-") (pintype "passive"))
      (node (ref "C20") (pin "1") (pinfunction "1_1") (pintype "passive"))
      (node (ref "C21") (pin "1") (pinfunction "1_1") (pintype "passive"))
      (node (ref "C22") (pin "1") (pinfunction "1_1") (pintype "passive"))
      (node (ref "C23") (pin "1") (pinfunction "1_1") (pintype "passive"))
      (node (ref "C24") (pin "1") (pinfunction "1_1") (pintype "passive"))
      (node (ref "C25") (pin "1") (pinfunction "1_1") (pintype "passive"))
      (node (ref "C26") (pin "1") (pinfunction "1_1") (pintype "passive"))
      (node (ref "C27") (pin "1") (pinfunction "1_1") (pintype "passive"))
      (node (ref "C28") (pin "2") (pinfunction "2_2") (pintype "passive"))
      (node (ref "C3") (pin "2") (pinfunction "2_2") (pintype "passive"))
      (node (ref "C4") (pin "2") (pinfunction "2_2") (pintype "passive"))
      (node (ref "C5") (pin "2") (pinfunction "2_2") (pintype "passive"))
      (node (ref "C6") (pin "2") (pinfunction "2_2") (pintype "passive"))
      (node (ref "C7") (pin "2") (pinfunction "2_2") (pintype "passive"))
      (node (ref "C8") (pin "2") (pinfunction "2_2") (pintype "passive"))
      (node (ref "CR1") (pin "2") (pinfunction "2_2") (pintype "passive"))
      (node (ref "DISPLAY") (pin "2") (pinfunction "2_2") (pintype "passive"))
      (node (ref "G1") (pin "1") (pinfunction "1_1") (pintype "passive"))
      (node (ref "G1") (pin "2") (pinfunction "2_2") (pintype "passive"))
      (node (ref "G1") (pin "3") (pinfunction "3_3") (pintype "passive"))
      (node (ref "HX1") (pin "1") (pinfunction "1_1") (pintype "passive"))
      (node (ref "HX1") (pin "7") (pinfunction "7_7") (pintype "passive"))
      (node (ref "HX2") (pin "2") (pinfunction "2_2") (pintype "passive"))
      (node (ref "HX2") (pin "3") (pinfunction "3_3") (pintype "passive"))
      (node (ref "HY1") (pin "1") (pinfunction "1_1") (pintype "passive"))
      (node (ref "HY1") (pin "7") (pinfunction "7_7") (pintype "passive"))
      (node (ref "HY2") (pin "3") (pinfunction "3_3") (pintype "passive"))
      (node (ref "HZ1") (pin "1") (pinfunction "1_1") (pintype "passive"))
      (node (ref "HZ1") (pin "7") (pinfunction "7_7") (pintype "passive"))
      (node (ref "HZ2") (pin "2") (pinfunction "2_2") (pintype "passive"))
      (node (ref "J5") (pin "10") (pinfunction "10_10") (pintype "passive"))
      (node (ref "J5") (pin "2") (pinfunction "2_2") (pintype "passive"))
      (node (ref "J5") (pin "4") (pinfunction "4_4") (pintype "passive"))
      (node (ref "J5") (pin "6") (pinfunction "6_6") (pintype "passive"))
      (node (ref "J5") (pin "8") (pinfunction "8_8") (pintype "passive"))
      (node (ref "R23") (pin "1") (pinfunction "1_1") (pintype "passive"))
      (node (ref "R25") (pin "1") (pinfunction "1_1") (pintype "passive"))
      (node (ref "S1") (pin "C") (pinfunction "C_C") (pintype "bidirectional"))
      (node (ref "S1") (pin "SW-") (pinfunction "SW-_SW-") (pintype "bidirectional"))
      (node (ref "SEN0") (pin "3") (pinfunction "3_3") (pintype "passive"))
      (node (ref "SEN0") (pin "5") (pinfunction "5_5") (pintype "passive"))
      (node (ref "SEN0") (pin "7") (pinfunction "7_7") (pintype "passive"))
      (node (ref "SEN0") (pin "P1") (pinfunction "SHIELD_P1") (pintype "passive"))
      (node (ref "SEN0") (pin "P2") (pinfunction "SHIELD_P2") (pintype "passive"))
      (node (ref "SEN0-S") (pin "3") (pinfunction "3_3") (pintype "passive"))
      (node (ref "SEN0-S") (pin "5") (pinfunction "5_5") (pintype "passive"))
      (node (ref "SEN0-S") (pin "7") (pinfunction "7_7") (pintype "passive"))
      (node (ref "SEN1") (pin "3") (pinfunction "3_3") (pintype "passive"))
      (node (ref "SEN1") (pin "5") (pinfunction "5_5") (pintype "passive"))
      (node (ref "SEN1") (pin "7") (pinfunction "7_7") (pintype "passive"))
      (node (ref "SEN1") (pin "P1") (pinfunction "SHIELD_P1") (pintype "passive"))
      (node (ref "SEN1") (pin "P2") (pinfunction "SHIELD_P2") (pintype "passive"))
      (node (ref "SEN1-S") (pin "3") (pinfunction "3_3") (pintype "passive"))
      (node (ref "SEN1-S") (pin "5") (pinfunction "5_5") (pintype "passive"))
      (node (ref "SEN1-S") (pin "7") (pinfunction "7_7") (pintype "passive"))
      (node (ref "SEN2") (pin "3") (pinfunction "3_3") (pintype "passive"))
      (node (ref "SEN2") (pin "5") (pinfunction "5_5") (pintype "passive"))
      (node (ref "SEN2") (pin "7") (pinfunction "7_7") (pintype "passive"))
      (node (ref "SEN2") (pin "P1") (pinfunction "SHIELD_P1") (pintype "passive"))
      (node (ref "SEN2") (pin "P2") (pinfunction "SHIELD_P2") (pintype "passive"))
      (node (ref "SEN2-S") (pin "3") (pinfunction "3_3") (pintype "passive"))
      (node (ref "SEN2-S") (pin "5") (pinfunction "5_5") (pintype "passive"))
      (node (ref "SEN2-S") (pin "7") (pinfunction "7_7") (pintype "passive"))
      (node (ref "SEN3") (pin "3") (pinfunction "3_3") (pintype "passive"))
      (node (ref "SEN3") (pin "5") (pinfunction "5_5") (pintype "passive"))
      (node (ref "SEN3") (pin "7") (pinfunction "7_7") (pintype "passive"))
      (node (ref "SEN3") (pin "P1") (pinfunction "SHIELD_P1") (pintype "passive"))
      (node (ref "SEN3") (pin "P2") (pinfunction "SHIELD_P2") (pintype "passive"))
      (node (ref "SEN3-S") (pin "3") (pinfunction "3_3") (pintype "passive"))
      (node (ref "SEN3-S") (pin "5") (pinfunction "5_5") (pintype "passive"))
      (node (ref "SEN3-S") (pin "7") (pinfunction "7_7") (pintype "passive"))
      (node (ref "T1") (pin "10") (pinfunction "10_10") (pintype "passive"))
      (node (ref "T1") (pin "23") (pinfunction "23_23") (pintype "passive"))
      (node (ref "T2") (pin "1") (pinfunction "1_1") (pintype "passive"))
      (node (ref "T3") (pin "1") (pinfunction "1_1") (pintype "passive"))
      (node (ref "T4") (pin "1") (pinfunction "1_1") (pintype "passive"))
      (node (ref "T5") (pin "10") (pinfunction "10_10") (pintype "passive"))
      (node (ref "T5") (pin "23") (pinfunction "23_23") (pintype "passive"))
      (node (ref "T6") (pin "10") (pinfunction "10_10") (pintype "passive"))
      (node (ref "T6") (pin "23") (pinfunction "23_23") (pintype "passive"))
      (node (ref "U1") (pin "7") (pinfunction "GND_7") (pintype "power_in"))
      (node (ref "U1") (pin "EPAD") (pinfunction "EPAD_EPAD") (pintype "passive"))
    )
    (net (code "46") (name "Net-(C7-Pad1)") (class "Default")
      (node (ref "C7") (pin "1") (pinfunction "1_1") (pintype "passive"))
      (node (ref "R24") (pin "1") (pinfunction "1_1") (pintype "passive"))
    )
    (net (code "47") (name "Net-(HX1-Pad3)") (class "Default")
      (node (ref "HX1") (pin "3") (pinfunction "3_3") (pintype "passive"))
      (node (ref "X_OUT") (pin "1") (pinfunction "1_1") (pintype "bidirectional"))
    )
    (net (code "48") (name "Net-(HX1-Pad4)") (class "Default")
      (node (ref "HX1") (pin "4") (pinfunction "4_4") (pintype "passive"))
      (node (ref "X_OUT") (pin "2") (pinfunction "2_2") (pintype "bidirectional"))
    )
    (net (code "49") (name "Net-(HX1-Pad5)") (class "Default")
      (node (ref "HX1") (pin "5") (pinfunction "5_5") (pintype "passive"))
      (node (ref "X_OUT") (pin "3") (pinfunction "3_3") (pintype "bidirectional"))
    )
    (net (code "50") (name "Net-(HX1-Pad6)") (class "Default")
      (node (ref "HX1") (pin "6") (pinfunction "6_6") (pintype "passive"))
      (node (ref "X_OUT") (pin "4") (pinfunction "4_4") (pintype "bidirectional"))
    )
    (net (code "51") (name "Net-(HY1-Pad3)") (class "Default")
      (node (ref "HY1") (pin "3") (pinfunction "3_3") (pintype "passive"))
      (node (ref "Y_OUT") (pin "1") (pinfunction "1_1") (pintype "bidirectional"))
    )
    (net (code "52") (name "Net-(HY1-Pad4)") (class "Default")
      (node (ref "HY1") (pin "4") (pinfunction "4_4") (pintype "passive"))
      (node (ref "Y_OUT") (pin "2") (pinfunction "2_2") (pintype "bidirectional"))
    )
    (net (code "53") (name "Net-(HY1-Pad5)") (class "Default")
      (node (ref "HY1") (pin "5") (pinfunction "5_5") (pintype "passive"))
      (node (ref "Y_OUT") (pin "3") (pinfunction "3_3") (pintype "bidirectional"))
    )
    (net (code "54") (name "Net-(HY1-Pad6)") (class "Default")
      (node (ref "HY1") (pin "6") (pinfunction "6_6") (pintype "passive"))
      (node (ref "Y_OUT") (pin "4") (pinfunction "4_4") (pintype "bidirectional"))
    )
    (net (code "55") (name "Net-(HZ1-Pad3)") (class "Default")
      (node (ref "HZ1") (pin "3") (pinfunction "3_3") (pintype "passive"))
      (node (ref "Z_OUT") (pin "1") (pinfunction "1_1") (pintype "bidirectional"))
    )
    (net (code "56") (name "Net-(HZ1-Pad4)") (class "Default")
      (node (ref "HZ1") (pin "4") (pinfunction "4_4") (pintype "passive"))
      (node (ref "Z_OUT") (pin "2") (pinfunction "2_2") (pintype "bidirectional"))
    )
    (net (code "57") (name "Net-(HZ1-Pad5)") (class "Default")
      (node (ref "HZ1") (pin "5") (pinfunction "5_5") (pintype "passive"))
      (node (ref "Z_OUT") (pin "3") (pinfunction "3_3") (pintype "bidirectional"))
    )
    (net (code "58") (name "Net-(HZ1-Pad6)") (class "Default")
      (node (ref "HZ1") (pin "6") (pinfunction "6_6") (pintype "passive"))
      (node (ref "Z_OUT") (pin "4") (pinfunction "4_4") (pintype "bidirectional"))
    )
    (net (code "59") (name "Net-(R8-Pad1)") (class "Default")
      (node (ref "R8") (pin "1") (pinfunction "1_1") (pintype "passive"))
      (node (ref "T1") (pin "15") (pinfunction "15_15") (pintype "passive"))
      (node (ref "T5") (pin "15") (pinfunction "15_15") (pintype "passive"))
      (node (ref "T6") (pin "15") (pinfunction "15_15") (pintype "passive"))
    )
    (net (code "60") (name "Net-(T1-Pad2)") (class "Default")
      (node (ref "T1") (pin "2") (pinfunction "2_2") (pintype "passive"))
      (node (ref "T5") (pin "2") (pinfunction "2_2") (pintype "passive"))
      (node (ref "T6") (pin "2") (pinfunction "2_2") (pintype "passive"))
    )
    (net (code "61") (name "Net-(T1-Pad3)") (class "Default")
      (node (ref "T1") (pin "3") (pinfunction "3_3") (pintype "passive"))
      (node (ref "T5") (pin "3") (pinfunction "3_3") (pintype "passive"))
      (node (ref "T6") (pin "3") (pinfunction "3_3") (pintype "passive"))
    )
    (net (code "62") (name "Net-(T1-Pad5)") (class "Default")
      (node (ref "T1") (pin "5") (pinfunction "5_5") (pintype "passive"))
      (node (ref "T5") (pin "5") (pinfunction "5_5") (pintype "passive"))
      (node (ref "T6") (pin "5") (pinfunction "5_5") (pintype "passive"))
    )
    (net (code "63") (name "Net-(T1-Pad8)") (class "Default")
      (node (ref "T1") (pin "8") (pinfunction "8_8") (pintype "passive"))
      (node (ref "T5") (pin "8") (pinfunction "8_8") (pintype "passive"))
      (node (ref "T6") (pin "8") (pinfunction "8_8") (pintype "passive"))
    )
    (net (code "64") (name "Net-(T1-Pad12)") (class "Default")
      (node (ref "T1") (pin "12") (pinfunction "12_12") (pintype "passive"))
      (node (ref "T5") (pin "12") (pinfunction "12_12") (pintype "passive"))
      (node (ref "T6") (pin "12") (pinfunction "12_12") (pintype "passive"))
    )
    (net (code "65") (name "Net-(T1-Pad18)") (class "Default")
      (node (ref "T1") (pin "18") (pinfunction "18_18") (pintype "passive"))
      (node (ref "T5") (pin "18") (pinfunction "18_18") (pintype "passive"))
      (node (ref "T6") (pin "18") (pinfunction "18_18") (pintype "passive"))
    )
    (net (code "66") (name "Net-(T2-Pad2)") (class "Default")
      (node (ref "T2") (pin "2") (pinfunction "2_2") (pintype "passive"))
      (node (ref "T3") (pin "2") (pinfunction "2_2") (pintype "passive"))
      (node (ref "T4") (pin "2") (pinfunction "2_2") (pintype "passive"))
    )
    (net (code "67") (name "Net-(T2-Pad3)") (class "Default")
      (node (ref "T2") (pin "3") (pinfunction "3_3") (pintype "passive"))
      (node (ref "T3") (pin "3") (pinfunction "3_3") (pintype "passive"))
      (node (ref "T4") (pin "3") (pinfunction "3_3") (pintype "passive"))
    )
    (net (code "68") (name "Net-(T2-Pad10)") (class "Default")
      (node (ref "T2") (pin "10") (pinfunction "10_10") (pintype "passive"))
      (node (ref "T3") (pin "10") (pinfunction "10_10") (pintype "passive"))
      (node (ref "T4") (pin "10") (pinfunction "10_10") (pintype "passive"))
    )
    (net (code "69") (name "Net-(T2-Pad11)") (class "Default")
      (node (ref "T2") (pin "11") (pinfunction "11_11") (pintype "passive"))
      (node (ref "T3") (pin "11") (pinfunction "11_11") (pintype "passive"))
      (node (ref "T4") (pin "11") (pinfunction "11_11") (pintype "passive"))
    )
    (net (code "70") (name "Net-(U1-BOOT)") (class "Default")
      (node (ref "C9") (pin "1") (pinfunction "1_1") (pintype "passive"))
      (node (ref "U1") (pin "1") (pinfunction "BOOT_1") (pintype "output"))
    )
    (net (code "71") (name "Net-(U1-COMP)") (class "Default")
      (node (ref "C8") (pin "1") (pinfunction "1_1") (pintype "passive"))
      (node (ref "R24") (pin "2") (pinfunction "2_2") (pintype "passive"))
      (node (ref "U1") (pin "6") (pinfunction "COMP_6") (pintype "output"))
    )
    (net (code "72") (name "Net-(U1-FB)") (class "Default")
      (node (ref "R25") (pin "2") (pinfunction "2_2") (pintype "passive"))
      (node (ref "R26") (pin "1") (pinfunction "1_1") (pintype "passive"))
      (node (ref "U1") (pin "5") (pinfunction "FB_5") (pintype "input"))
    )
    (net (code "73") (name "Net-(U1-RT{slash}CLK)") (class "Default")
      (node (ref "R23") (pin "2") (pinfunction "2_2") (pintype "passive"))
      (node (ref "U1") (pin "4") (pinfunction "RT/CLK_4") (pintype "input"))
    )
    (net (code "74") (name "Net-(U1-SW)") (class "Default")
      (node (ref "C9") (pin "2") (pinfunction "2_2") (pintype "passive"))
      (node (ref "CR1") (pin "1") (pinfunction "1_1") (pintype "passive"))
      (node (ref "L1") (pin "1") (pinfunction "1_1") (pintype "passive"))
      (node (ref "U1") (pin "8") (pinfunction "SW_8") (pintype "input"))
    )
    (net (code "75") (name "unconnected-(HX2-Pad5)") (class "Default")
      (node (ref "HX2") (pin "5") (pinfunction "5_5") (pintype "passive"))
    )
    (net (code "76") (name "unconnected-(HX2-Pad6)") (class "Default")
      (node (ref "HX2") (pin "6") (pinfunction "6_6") (pintype "passive"))
    )
    (net (code "77") (name "unconnected-(HY2-Pad5)") (class "Default")
      (node (ref "HY2") (pin "5") (pinfunction "5_5") (pintype "passive"))
    )
    (net (code "78") (name "unconnected-(HY2-Pad6)") (class "Default")
      (node (ref "HY2") (pin "6") (pinfunction "6_6") (pintype "passive"))
    )
    (net (code "79") (name "unconnected-(HZ2-Pad5)") (class "Default")
      (node (ref "HZ2") (pin "5") (pinfunction "5_5") (pintype "passive"))
    )
    (net (code "80") (name "unconnected-(HZ2-Pad6)") (class "Default")
      (node (ref "HZ2") (pin "6") (pinfunction "6_6") (pintype "passive"))
    )
    (net (code "81") (name "unconnected-(U1-EN-Pad3)") (class "Default")
      (node (ref "U1") (pin "3") (pinfunction "EN_3") (pintype "input"))
    )
  )
)
